# main_schematic.net
KiCad netlist of a schematic drawn in Altium Designer
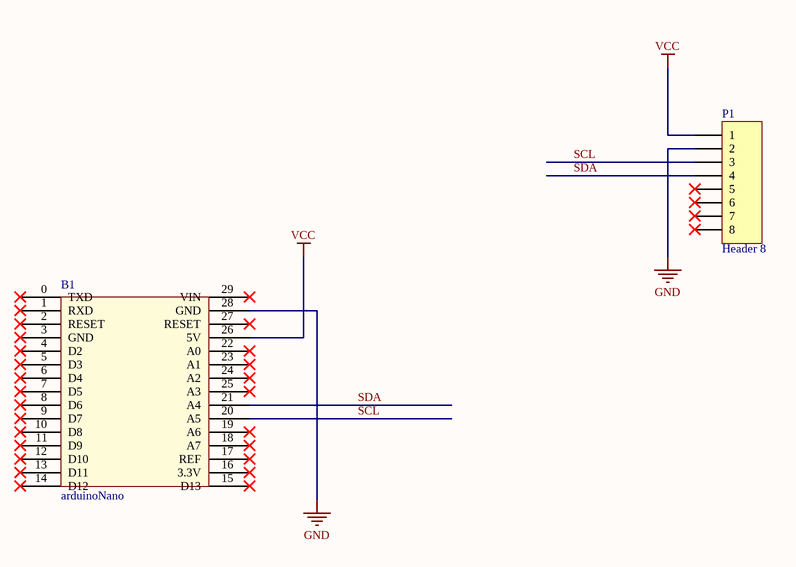
[diagram p0: main_schematic.SchDoc]

(export (version "E")
  (design (tool "Eeschema 10.0.6"))
  (components
    (comp (ref "B1")
      (value "arduinoNano")
      (footprint "Arduino nano")
      (libsource (lib "nanoArduino") (part "arduinoNano"))
    )
    (comp (ref "P1")
      (value "Header 8")
      (footprint "HDR1X8")
      (description "Header, 8-Pin")
      (fields (field (name "PUBLISHER") "Altium Limited"))
      (libsource (lib "Miscellaneous Connectors") (part "Header 8"))
    )
  )
  (nets
    (net (code "1") (name "/SCL") (class "Default")
      (node (ref "B1") (pin "20") (pinfunction "A5_20") (pintype "passive"))
      (node (ref "P1") (pin "3") (pinfunction "3_3") (pintype "passive"))
    )
    (net (code "2") (name "/SDA") (class "Default")
      (node (ref "B1") (pin "21") (pinfunction "A4_21") (pintype "passive"))
      (node (ref "P1") (pin "4") (pinfunction "4_4") (pintype "passive"))
    )
    (net (code "3") (name "GND") (class "Default")
      (node (ref "B1") (pin "28") (pinfunction "GND_28") (pintype "passive"))
      (node (ref "P1") (pin "2") (pinfunction "2_2") (pintype "passive"))
    )
    (net (code "4") (name "VCC") (class "Default")
      (node (ref "B1") (pin "26") (pinfunction "5V_26") (pintype "passive"))
      (node (ref "P1") (pin "1") (pinfunction "1_1") (pintype "passive"))
    )
    (net (code "5") (name "unconnected-(B1-3.3V-Pad16)") (class "Default")
      (node (ref "B1") (pin "16") (pinfunction "3.3V_16") (pintype "passive+no_connect"))
    )
    (net (code "6") (name "unconnected-(B1-A0-Pad22)") (class "Default")
      (node (ref "B1") (pin "22") (pinfunction "A0_22") (pintype "passive+no_connect"))
    )
    (net (code "7") (name "unconnected-(B1-A1-Pad23)") (class "Default")
      (node (ref "B1") (pin "23") (pinfunction "A1_23") (pintype "passive+no_connect"))
    )
    (net (code "8") (name "unconnected-(B1-A2-Pad24)") (class "Default")
      (node (ref "B1") (pin "24") (pinfunction "A2_24") (pintype "passive+no_connect"))
    )
    (net (code "9") (name "unconnected-(B1-A3-Pad25)") (class "Default")
      (node (ref "B1") (pin "25") (pinfunction "A3_25") (pintype "passive+no_connect"))
    )
    (net (code "10") (name "unconnected-(B1-A6-Pad19)") (class "Default")
      (node (ref "B1") (pin "19") (pinfunction "A6_19") (pintype "passive+no_connect"))
    )
    (net (code "11") (name "unconnected-(B1-A7-Pad18)") (class "Default")
      (node (ref "B1") (pin "18") (pinfunction "A7_18") (pintype "passive+no_connect"))
    )
    (net (code "12") (name "unconnected-(B1-D2-Pad4)") (class "Default")
      (node (ref "B1") (pin "4") (pinfunction "D2_4") (pintype "passive+no_connect"))
    )
    (net (code "13") (name "unconnected-(B1-D3-Pad5)") (class "Default")
      (node (ref "B1") (pin "5") (pinfunction "D3_5") (pintype "passive+no_connect"))
    )
    (net (code "14") (name "unconnected-(B1-D4-Pad6)") (class "Default")
      (node (ref "B1") (pin "6") (pinfunction "D4_6") (pintype "passive+no_connect"))
    )
    (net (code "15") (name "unconnected-(B1-D5-Pad7)") (class "Default")
      (node (ref "B1") (pin "7") (pinfunction "D5_7") (pintype "passive+no_connect"))
    )
    (net (code "16") (name "unconnected-(B1-D6-Pad8)") (class "Default")
      (node (ref "B1") (pin "8") (pinfunction "D6_8") (pintype "passive+no_connect"))
    )
    (net (code "17") (name "unconnected-(B1-D7-Pad9)") (class "Default")
      (node (ref "B1") (pin "9") (pinfunction "D7_9") (pintype "passive+no_connect"))
    )
    (net (code "18") (name "unconnected-(B1-D8-Pad10)") (class "Default")
      (node (ref "B1") (pin "10") (pinfunction "D8_10") (pintype "passive+no_connect"))
    )
    (net (code "19") (name "unconnected-(B1-D9-Pad11)") (class "Default")
      (node (ref "B1") (pin "11") (pinfunction "D9_11") (pintype "passive+no_connect"))
    )
    (net (code "20") (name "unconnected-(B1-D10-Pad12)") (class "Default")
      (node (ref "B1") (pin "12") (pinfunction "D10_12") (pintype "passive+no_connect"))
    )
    (net (code "21") (name "unconnected-(B1-D11-Pad13)") (class "Default")
      (node (ref "B1") (pin "13") (pinfunction "D11_13") (pintype "passive+no_connect"))
    )
    (net (code "22") (name "unconnected-(B1-D12-Pad14)") (class "Default")
      (node (ref "B1") (pin "14") (pinfunction "D12_14") (pintype "passive+no_connect"))
    )
    (net (code "23") (name "unconnected-(B1-D13-Pad15)") (class "Default")
      (node (ref "B1") (pin "15") (pinfunction "D13_15") (pintype "passive+no_connect"))
    )
    (net (code "24") (name "unconnected-(B1-GND-Pad3)") (class "Default")
      (node (ref "B1") (pin "3") (pinfunction "GND_3") (pintype "passive+no_connect"))
    )
    (net (code "25") (name "unconnected-(B1-REF-Pad17)") (class "Default")
      (node (ref "B1") (pin "17") (pinfunction "REF_17") (pintype "passive+no_connect"))
    )
    (net (code "26") (name "unconnected-(B1-RESET-Pad2)") (class "Default")
      (node (ref "B1") (pin "2") (pinfunction "RESET_2") (pintype "passive+no_connect"))
    )
    (net (code "27") (name "unconnected-(B1-RESET-Pad27)") (class "Default")
      (node (ref "B1") (pin "27") (pinfunction "RESET_27") (pintype "passive+no_connect"))
    )
    (net (code "28") (name "unconnected-(B1-RXD-Pad1)") (class "Default")
      (node (ref "B1") (pin "1") (pinfunction "RXD_1") (pintype "passive+no_connect"))
    )
    (net (code "29") (name "unconnected-(B1-TXD-Pad0)") (class "Default")
      (node (ref "B1") (pin "0") (pinfunction "TXD_0") (pintype "passive+no_connect"))
    )
    (net (code "30") (name "unconnected-(B1-VIN-Pad29)") (class "Default")
      (node (ref "B1") (pin "29") (pinfunction "VIN_29") (pintype "passive+no_connect"))
    )
    (net (code "31") (name "unconnected-(P1-Pad5)") (class "Default")
      (node (ref "P1") (pin "5") (pinfunction "5_5") (pintype "passive+no_connect"))
    )
    (net (code "32") (name "unconnected-(P1-Pad6)") (class "Default")
      (node (ref "P1") (pin "6") (pinfunction "6_6") (pintype "passive+no_connect"))
    )
    (net (code "33") (name "unconnected-(P1-Pad7)") (class "Default")
      (node (ref "P1") (pin "7") (pinfunction "7_7") (pintype "passive+no_connect"))
    )
    (net (code "34") (name "unconnected-(P1-Pad8)") (class "Default")
      (node (ref "P1") (pin "8") (pinfunction "8_8") (pintype "passive+no_connect"))
    )
  )
)
